# Power.net
KiCad netlist of a schematic drawn in Altium Designer
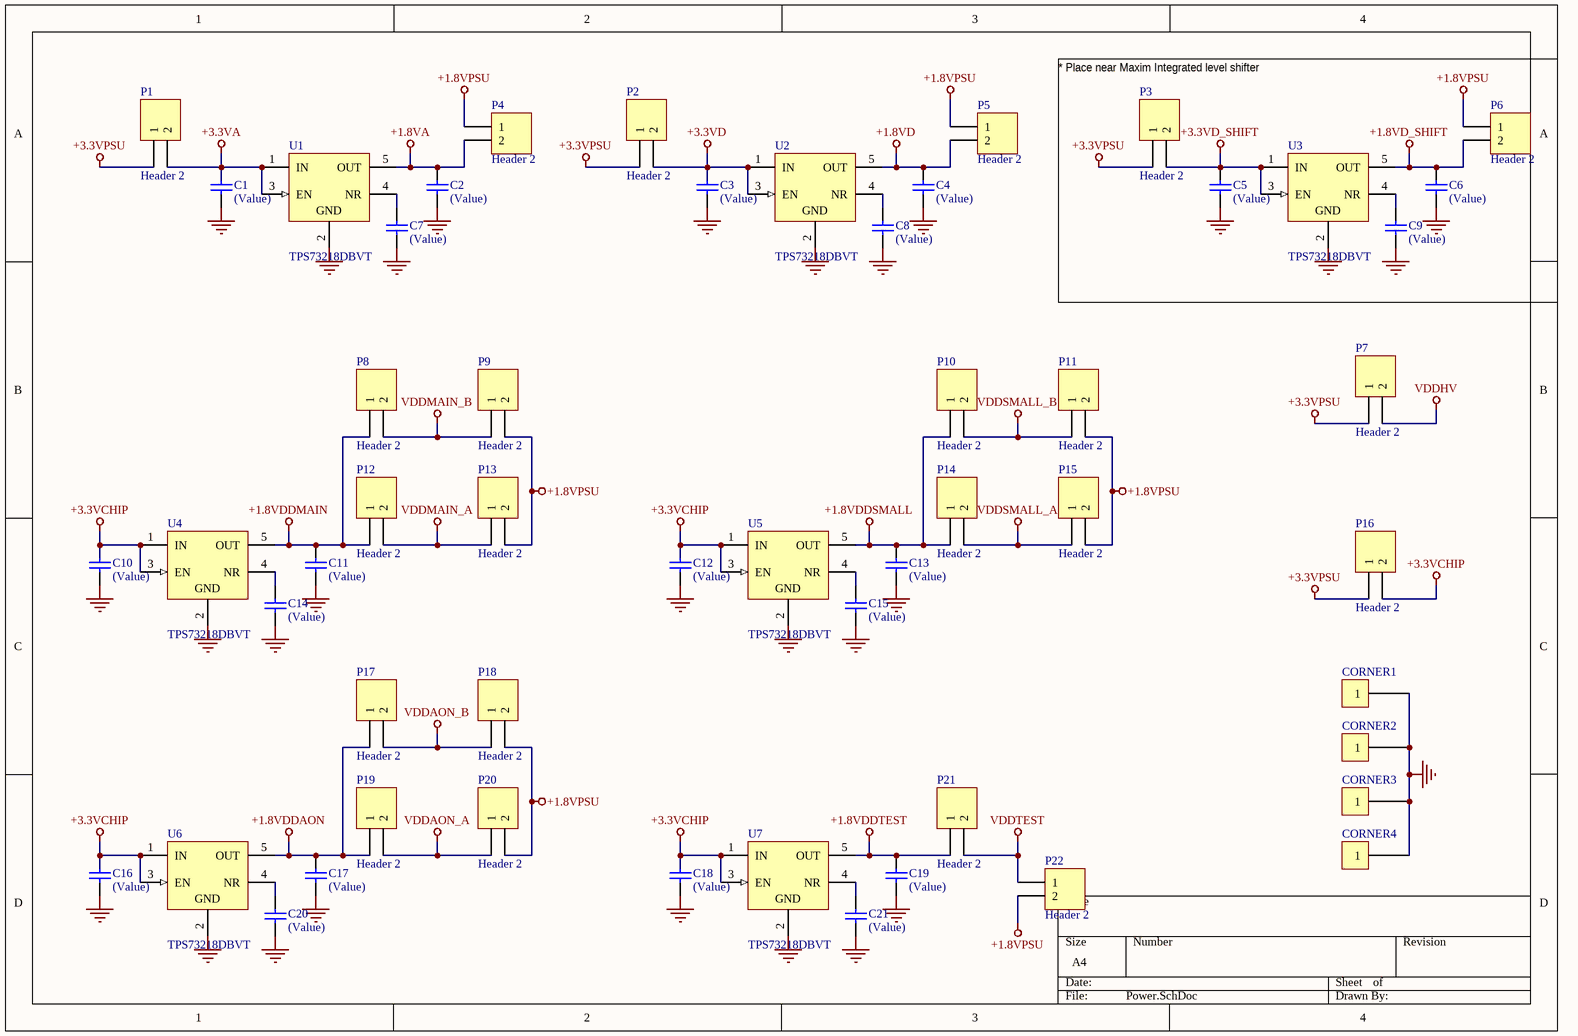
[diagram p0: Power.SchDoc]

(export (version "E")
  (design (tool "Eeschema 10.0.6"))
  (components
    (comp (ref "C1")
      (value "(Value)")
      (footprint "CAPC1608X90X35ML10T15")
      (description "0603")
      (fields (field (name "MANUFACTURER") "Murata"))
      (libsource (lib "Altium Content Vault") (part "CAP-NP-2"))
    )
    (comp (ref "C2")
      (value "(Value)")
      (footprint "CAPC1608X90X35ML10T15")
      (description "0603")
      (fields (field (name "MANUFACTURER") "Murata"))
      (libsource (lib "Altium Content Vault") (part "CAP-NP-2"))
    )
    (comp (ref "C3")
      (value "(Value)")
      (footprint "CAPC1608X90X35ML10T15")
      (description "0603")
      (fields (field (name "MANUFACTURER") "Murata"))
      (libsource (lib "Altium Content Vault") (part "CAP-NP-2"))
    )
    (comp (ref "C4")
      (value "(Value)")
      (footprint "CAPC1608X90X35ML10T15")
      (description "0603")
      (fields (field (name "MANUFACTURER") "Murata"))
      (libsource (lib "Altium Content Vault") (part "CAP-NP-2"))
    )
    (comp (ref "C5")
      (value "(Value)")
      (footprint "CAPC1608X90X35ML10T15")
      (description "0603")
      (fields (field (name "MANUFACTURER") "Murata"))
      (libsource (lib "Altium Content Vault") (part "CAP-NP-2"))
    )
    (comp (ref "C6")
      (value "(Value)")
      (footprint "CAPC1608X90X35ML10T15")
      (description "0603")
      (fields (field (name "MANUFACTURER") "Murata"))
      (libsource (lib "Altium Content Vault") (part "CAP-NP-2"))
    )
    (comp (ref "C7")
      (value "(Value)")
      (footprint "CAPC1608X90X35ML10T15")
      (description "0603")
      (fields (field (name "MANUFACTURER") "Murata"))
      (libsource (lib "Altium Content Vault") (part "CAP-NP-2"))
    )
    (comp (ref "C8")
      (value "(Value)")
      (footprint "CAPC1608X90X35ML10T15")
      (description "0603")
      (fields (field (name "MANUFACTURER") "Murata"))
      (libsource (lib "Altium Content Vault") (part "CAP-NP-2"))
    )
    (comp (ref "C9")
      (value "(Value)")
      (footprint "CAPC1608X90X35ML10T15")
      (description "0603")
      (fields (field (name "MANUFACTURER") "Murata"))
      (libsource (lib "Altium Content Vault") (part "CAP-NP-2"))
    )
    (comp (ref "C10")
      (value "(Value)")
      (footprint "CAPC1608X90X35ML10T15")
      (description "0603")
      (fields (field (name "MANUFACTURER") "Murata"))
      (libsource (lib "Altium Content Vault") (part "CAP-NP-2"))
    )
    (comp (ref "C11")
      (value "(Value)")
      (footprint "CAPC1608X90X35ML10T15")
      (description "0603")
      (fields (field (name "MANUFACTURER") "Murata"))
      (libsource (lib "Altium Content Vault") (part "CAP-NP-2"))
    )
    (comp (ref "C12")
      (value "(Value)")
      (footprint "CAPC1608X90X35ML10T15")
      (description "0603")
      (fields (field (name "MANUFACTURER") "Murata"))
      (libsource (lib "Altium Content Vault") (part "CAP-NP-2"))
    )
    (comp (ref "C13")
      (value "(Value)")
      (footprint "CAPC1608X90X35ML10T15")
      (description "0603")
      (fields (field (name "MANUFACTURER") "Murata"))
      (libsource (lib "Altium Content Vault") (part "CAP-NP-2"))
    )
    (comp (ref "C14")
      (value "(Value)")
      (footprint "CAPC1608X90X35ML10T15")
      (description "0603")
      (fields (field (name "MANUFACTURER") "Murata"))
      (libsource (lib "Altium Content Vault") (part "CAP-NP-2"))
    )
    (comp (ref "C15")
      (value "(Value)")
      (footprint "CAPC1608X90X35ML10T15")
      (description "0603")
      (fields (field (name "MANUFACTURER") "Murata"))
      (libsource (lib "Altium Content Vault") (part "CAP-NP-2"))
    )
    (comp (ref "C16")
      (value "(Value)")
      (footprint "CAPC1608X90X35ML10T15")
      (description "0603")
      (fields (field (name "MANUFACTURER") "Murata"))
      (libsource (lib "Altium Content Vault") (part "CAP-NP-2"))
    )
    (comp (ref "C17")
      (value "(Value)")
      (footprint "CAPC1608X90X35ML10T15")
      (description "0603")
      (fields (field (name "MANUFACTURER") "Murata"))
      (libsource (lib "Altium Content Vault") (part "CAP-NP-2"))
    )
    (comp (ref "C18")
      (value "(Value)")
      (footprint "CAPC1608X90X35ML10T15")
      (description "0603")
      (fields (field (name "MANUFACTURER") "Murata"))
      (libsource (lib "Altium Content Vault") (part "CAP-NP-2"))
    )
    (comp (ref "C19")
      (value "(Value)")
      (footprint "CAPC1608X90X35ML10T15")
      (description "0603")
      (fields (field (name "MANUFACTURER") "Murata"))
      (libsource (lib "Altium Content Vault") (part "CAP-NP-2"))
    )
    (comp (ref "C20")
      (value "(Value)")
      (footprint "CAPC1608X90X35ML10T15")
      (description "0603")
      (fields (field (name "MANUFACTURER") "Murata"))
      (libsource (lib "Altium Content Vault") (part "CAP-NP-2"))
    )
    (comp (ref "C21")
      (value "(Value)")
      (footprint "CAPC1608X90X35ML10T15")
      (description "0603")
      (fields (field (name "MANUFACTURER") "Murata"))
      (libsource (lib "Altium Content Vault") (part "CAP-NP-2"))
    )
    (comp (ref "CORNER1")
      (value "Corner Mount")
      (footprint "CornerMount")
      (libsource (lib "intlib") (part "Corner Mount"))
    )
    (comp (ref "CORNER2")
      (value "Corner Mount")
      (footprint "CornerMount")
      (libsource (lib "intlib") (part "Corner Mount"))
    )
    (comp (ref "CORNER3")
      (value "Corner Mount")
      (footprint "CornerMount")
      (libsource (lib "intlib") (part "Corner Mount"))
    )
    (comp (ref "CORNER4")
      (value "Corner Mount")
      (footprint "CornerMount")
      (libsource (lib "intlib") (part "Corner Mount"))
    )
    (comp (ref "P1")
      (value "Header 2")
      (footprint "HDR1X2")
      (description "Header, 2-Pin")
      (fields (field (name "PUBLISHER") "Altium Limited"))
      (libsource (lib "Miscellaneous Connectors") (part "Header 2"))
    )
    (comp (ref "P2")
      (value "Header 2")
      (footprint "HDR1X2")
      (description "Header, 2-Pin")
      (fields (field (name "PUBLISHER") "Altium Limited"))
      (libsource (lib "Miscellaneous Connectors") (part "Header 2"))
    )
    (comp (ref "P3")
      (value "Header 2")
      (footprint "HDR1X2")
      (description "Header, 2-Pin")
      (fields (field (name "PUBLISHER") "Altium Limited"))
      (libsource (lib "Miscellaneous Connectors") (part "Header 2"))
    )
    (comp (ref "P4")
      (value "Header 2")
      (footprint "HDR1X2")
      (description "Header, 2-Pin")
      (fields (field (name "PUBLISHER") "Altium Limited"))
      (libsource (lib "") (part "Header 2_1"))
    )
    (comp (ref "P5")
      (value "Header 2")
      (footprint "HDR1X2")
      (description "Header, 2-Pin")
      (fields (field (name "PUBLISHER") "Altium Limited"))
      (libsource (lib "") (part "Header 2_1"))
    )
    (comp (ref "P6")
      (value "Header 2")
      (footprint "HDR1X2")
      (description "Header, 2-Pin")
      (fields (field (name "PUBLISHER") "Altium Limited"))
      (libsource (lib "") (part "Header 2_1"))
    )
    (comp (ref "P7")
      (value "Header 2")
      (footprint "HDR1X2")
      (description "Header, 2-Pin")
      (fields (field (name "PUBLISHER") "Altium Limited"))
      (libsource (lib "Miscellaneous Connectors") (part "Header 2"))
    )
    (comp (ref "P8")
      (value "Header 2")
      (footprint "HDR1X2")
      (description "Header, 2-Pin")
      (fields (field (name "PUBLISHER") "Altium Limited"))
      (libsource (lib "Miscellaneous Connectors") (part "Header 2"))
    )
    (comp (ref "P9")
      (value "Header 2")
      (footprint "HDR1X2")
      (description "Header, 2-Pin")
      (fields (field (name "PUBLISHER") "Altium Limited"))
      (libsource (lib "Miscellaneous Connectors") (part "Header 2"))
    )
    (comp (ref "P10")
      (value "Header 2")
      (footprint "HDR1X2")
      (description "Header, 2-Pin")
      (fields (field (name "PUBLISHER") "Altium Limited"))
      (libsource (lib "Miscellaneous Connectors") (part "Header 2"))
    )
    (comp (ref "P11")
      (value "Header 2")
      (footprint "HDR1X2")
      (description "Header, 2-Pin")
      (fields (field (name "PUBLISHER") "Altium Limited"))
      (libsource (lib "Miscellaneous Connectors") (part "Header 2"))
    )
    (comp (ref "P12")
      (value "Header 2")
      (footprint "HDR1X2")
      (description "Header, 2-Pin")
      (fields (field (name "PUBLISHER") "Altium Limited"))
      (libsource (lib "Miscellaneous Connectors") (part "Header 2"))
    )
    (comp (ref "P13")
      (value "Header 2")
      (footprint "HDR1X2")
      (description "Header, 2-Pin")
      (fields (field (name "PUBLISHER") "Altium Limited"))
      (libsource (lib "Miscellaneous Connectors") (part "Header 2"))
    )
    (comp (ref "P14")
      (value "Header 2")
      (footprint "HDR1X2")
      (description "Header, 2-Pin")
      (fields (field (name "PUBLISHER") "Altium Limited"))
      (libsource (lib "Miscellaneous Connectors") (part "Header 2"))
    )
    (comp (ref "P15")
      (value "Header 2")
      (footprint "HDR1X2")
      (description "Header, 2-Pin")
      (fields (field (name "PUBLISHER") "Altium Limited"))
      (libsource (lib "Miscellaneous Connectors") (part "Header 2"))
    )
    (comp (ref "P16")
      (value "Header 2")
      (footprint "HDR1X2")
      (description "Header, 2-Pin")
      (fields (field (name "PUBLISHER") "Altium Limited"))
      (libsource (lib "Miscellaneous Connectors") (part "Header 2"))
    )
    (comp (ref "P17")
      (value "Header 2")
      (footprint "HDR1X2")
      (description "Header, 2-Pin")
      (fields (field (name "PUBLISHER") "Altium Limited"))
      (libsource (lib "Miscellaneous Connectors") (part "Header 2"))
    )
    (comp (ref "P18")
      (value "Header 2")
      (footprint "HDR1X2")
      (description "Header, 2-Pin")
      (fields (field (name "PUBLISHER") "Altium Limited"))
      (libsource (lib "Miscellaneous Connectors") (part "Header 2"))
    )
    (comp (ref "P19")
      (value "Header 2")
      (footprint "HDR1X2")
      (description "Header, 2-Pin")
      (fields (field (name "PUBLISHER") "Altium Limited"))
      (libsource (lib "Miscellaneous Connectors") (part "Header 2"))
    )
    (comp (ref "P20")
      (value "Header 2")
      (footprint "HDR1X2")
      (description "Header, 2-Pin")
      (fields (field (name "PUBLISHER") "Altium Limited"))
      (libsource (lib "Miscellaneous Connectors") (part "Header 2"))
    )
    (comp (ref "P21")
      (value "Header 2")
      (footprint "HDR1X2")
      (description "Header, 2-Pin")
      (fields (field (name "PUBLISHER") "Altium Limited"))
      (libsource (lib "Miscellaneous Connectors") (part "Header 2"))
    )
    (comp (ref "P22")
      (value "Header 2")
      (footprint "HDR1X2")
      (description "Header, 2-Pin")
      (fields (field (name "PUBLISHER") "Altium Limited"))
      (libsource (lib "") (part "Header 2_1"))
    )
    (comp (ref "U1")
      (value "TPS73218DBVT")
      (footprint "DBV0005A_N")
      (fields (field (name "MANUFACTURER") "Texas Instruments"))
      (libsource (lib "Altium Content Vault") (part "TI-TPS79NXX-YYSOT5"))
    )
    (comp (ref "U2")
      (value "TPS73218DBVT")
      (footprint "DBV0005A_N")
      (fields (field (name "MANUFACTURER") "Texas Instruments"))
      (libsource (lib "Altium Content Vault") (part "TI-TPS79NXX-YYSOT5"))
    )
    (comp (ref "U3")
      (value "TPS73218DBVT")
      (footprint "DBV0005A_N")
      (fields (field (name "MANUFACTURER") "Texas Instruments"))
      (libsource (lib "Altium Content Vault") (part "TI-TPS79NXX-YYSOT5"))
    )
    (comp (ref "U4")
      (value "TPS73218DBVT")
      (footprint "DBV0005A_N")
      (fields (field (name "MANUFACTURER") "Texas Instruments"))
      (libsource (lib "Altium Content Vault") (part "TI-TPS79NXX-YYSOT5"))
    )
    (comp (ref "U5")
      (value "TPS73218DBVT")
      (footprint "DBV0005A_N")
      (fields (field (name "MANUFACTURER") "Texas Instruments"))
      (libsource (lib "Altium Content Vault") (part "TI-TPS79NXX-YYSOT5"))
    )
    (comp (ref "U6")
      (value "TPS73218DBVT")
      (footprint "DBV0005A_N")
      (fields (field (name "MANUFACTURER") "Texas Instruments"))
      (libsource (lib "Altium Content Vault") (part "TI-TPS79NXX-YYSOT5"))
    )
    (comp (ref "U7")
      (value "TPS73218DBVT")
      (footprint "DBV0005A_N")
      (fields (field (name "MANUFACTURER") "Texas Instruments"))
      (libsource (lib "Altium Content Vault") (part "TI-TPS79NXX-YYSOT5"))
    )
  )
  (nets
    (net (code "1") (name "+1.8VA") (class "Default")
      (node (ref "C2") (pin "1") (pinfunction "1_1") (pintype "passive"))
      (node (ref "P4") (pin "2") (pinfunction "2_2") (pintype "passive"))
      (node (ref "U1") (pin "5") (pinfunction "OUT_5") (pintype "power_in"))
    )
    (net (code "2") (name "+1.8VD") (class "Default")
      (node (ref "C4") (pin "1") (pinfunction "1_1") (pintype "passive"))
      (node (ref "P5") (pin "2") (pinfunction "2_2") (pintype "passive"))
      (node (ref "U2") (pin "5") (pinfunction "OUT_5") (pintype "power_in"))
    )
    (net (code "3") (name "+1.8VDDAON") (class "Default")
      (node (ref "C17") (pin "1") (pinfunction "1_1") (pintype "passive"))
      (node (ref "P17") (pin "1") (pinfunction "1_1") (pintype "passive"))
      (node (ref "P19") (pin "1") (pinfunction "1_1") (pintype "passive"))
      (node (ref "U6") (pin "5") (pinfunction "OUT_5") (pintype "power_in"))
    )
    (net (code "4") (name "+1.8VDDMAIN") (class "Default")
      (node (ref "C11") (pin "1") (pinfunction "1_1") (pintype "passive"))
      (node (ref "P12") (pin "1") (pinfunction "1_1") (pintype "passive"))
      (node (ref "P8") (pin "1") (pinfunction "1_1") (pintype "passive"))
      (node (ref "U4") (pin "5") (pinfunction "OUT_5") (pintype "power_in"))
    )
    (net (code "5") (name "+1.8VDDSMALL") (class "Default")
      (node (ref "C13") (pin "1") (pinfunction "1_1") (pintype "passive"))
      (node (ref "P10") (pin "1") (pinfunction "1_1") (pintype "passive"))
      (node (ref "P14") (pin "1") (pinfunction "1_1") (pintype "passive"))
      (node (ref "U5") (pin "5") (pinfunction "OUT_5") (pintype "power_in"))
    )
    (net (code "6") (name "+1.8VDDTEST") (class "Default")
      (node (ref "C19") (pin "1") (pinfunction "1_1") (pintype "passive"))
      (node (ref "P21") (pin "1") (pinfunction "1_1") (pintype "passive"))
      (node (ref "U7") (pin "5") (pinfunction "OUT_5") (pintype "power_in"))
    )
    (net (code "7") (name "+1.8VD_SHIFT") (class "Default")
      (node (ref "C6") (pin "1") (pinfunction "1_1") (pintype "passive"))
      (node (ref "P6") (pin "2") (pinfunction "2_2") (pintype "passive"))
      (node (ref "U3") (pin "5") (pinfunction "OUT_5") (pintype "power_in"))
    )
    (net (code "8") (name "+1.8VPSU") (class "Default")
      (node (ref "P11") (pin "2") (pinfunction "2_2") (pintype "passive"))
      (node (ref "P13") (pin "2") (pinfunction "2_2") (pintype "passive"))
      (node (ref "P15") (pin "2") (pinfunction "2_2") (pintype "passive"))
      (node (ref "P18") (pin "2") (pinfunction "2_2") (pintype "passive"))
      (node (ref "P20") (pin "2") (pinfunction "2_2") (pintype "passive"))
      (node (ref "P22") (pin "2") (pinfunction "2_2") (pintype "passive"))
      (node (ref "P4") (pin "1") (pinfunction "1_1") (pintype "passive"))
      (node (ref "P5") (pin "1") (pinfunction "1_1") (pintype "passive"))
      (node (ref "P6") (pin "1") (pinfunction "1_1") (pintype "passive"))
      (node (ref "P9") (pin "2") (pinfunction "2_2") (pintype "passive"))
    )
    (net (code "9") (name "+3.3VA") (class "Default")
      (node (ref "C1") (pin "1") (pinfunction "1_1") (pintype "passive"))
      (node (ref "P1") (pin "2") (pinfunction "2_2") (pintype "passive"))
      (node (ref "U1") (pin "1") (pinfunction "IN_1") (pintype "power_in"))
      (node (ref "U1") (pin "3") (pinfunction "EN_3") (pintype "input"))
    )
    (net (code "10") (name "+3.3VCHIP") (class "Default")
      (node (ref "C10") (pin "1") (pinfunction "1_1") (pintype "passive"))
      (node (ref "C12") (pin "1") (pinfunction "1_1") (pintype "passive"))
      (node (ref "C16") (pin "1") (pinfunction "1_1") (pintype "passive"))
      (node (ref "C18") (pin "1") (pinfunction "1_1") (pintype "passive"))
      (node (ref "P16") (pin "2") (pinfunction "2_2") (pintype "passive"))
      (node (ref "U4") (pin "1") (pinfunction "IN_1") (pintype "power_in"))
      (node (ref "U4") (pin "3") (pinfunction "EN_3") (pintype "input"))
      (node (ref "U5") (pin "1") (pinfunction "IN_1") (pintype "power_in"))
      (node (ref "U5") (pin "3") (pinfunction "EN_3") (pintype "input"))
      (node (ref "U6") (pin "1") (pinfunction "IN_1") (pintype "power_in"))
      (node (ref "U6") (pin "3") (pinfunction "EN_3") (pintype "input"))
      (node (ref "U7") (pin "1") (pinfunction "IN_1") (pintype "power_in"))
      (node (ref "U7") (pin "3") (pinfunction "EN_3") (pintype "input"))
    )
    (net (code "11") (name "+3.3VD") (class "Default")
      (node (ref "C3") (pin "1") (pinfunction "1_1") (pintype "passive"))
      (node (ref "P2") (pin "2") (pinfunction "2_2") (pintype "passive"))
      (node (ref "U2") (pin "1") (pinfunction "IN_1") (pintype "power_in"))
      (node (ref "U2") (pin "3") (pinfunction "EN_3") (pintype "input"))
    )
    (net (code "12") (name "+3.3VD_SHIFT") (class "Default")
      (node (ref "C5") (pin "1") (pinfunction "1_1") (pintype "passive"))
      (node (ref "P3") (pin "2") (pinfunction "2_2") (pintype "passive"))
      (node (ref "U3") (pin "1") (pinfunction "IN_1") (pintype "power_in"))
      (node (ref "U3") (pin "3") (pinfunction "EN_3") (pintype "input"))
    )
    (net (code "13") (name "+3.3VPSU") (class "Default")
      (node (ref "P1") (pin "1") (pinfunction "1_1") (pintype "passive"))
      (node (ref "P16") (pin "1") (pinfunction "1_1") (pintype "passive"))
      (node (ref "P2") (pin "1") (pinfunction "1_1") (pintype "passive"))
      (node (ref "P3") (pin "1") (pinfunction "1_1") (pintype "passive"))
      (node (ref "P7") (pin "1") (pinfunction "1_1") (pintype "passive"))
    )
    (net (code "14") (name "GND") (class "Default")
      (node (ref "C1") (pin "2") (pinfunction "2_2") (pintype "passive"))
      (node (ref "C10") (pin "2") (pinfunction "2_2") (pintype "passive"))
      (node (ref "C11") (pin "2") (pinfunction "2_2") (pintype "passive"))
      (node (ref "C12") (pin "2") (pinfunction "2_2") (pintype "passive"))
      (node (ref "C13") (pin "2") (pinfunction "2_2") (pintype "passive"))
      (node (ref "C14") (pin "2") (pinfunction "2_2") (pintype "passive"))
      (node (ref "C15") (pin "2") (pinfunction "2_2") (pintype "passive"))
      (node (ref "C16") (pin "2") (pinfunction "2_2") (pintype "passive"))
      (node (ref "C17") (pin "2") (pinfunction "2_2") (pintype "passive"))
      (node (ref "C18") (pin "2") (pinfunction "2_2") (pintype "passive"))
      (node (ref "C19") (pin "2") (pinfunction "2_2") (pintype "passive"))
      (node (ref "C2") (pin "2") (pinfunction "2_2") (pintype "passive"))
      (node (ref "C20") (pin "2") (pinfunction "2_2") (pintype "passive"))
      (node (ref "C21") (pin "2") (pinfunction "2_2") (pintype "passive"))
      (node (ref "C3") (pin "2") (pinfunction "2_2") (pintype "passive"))
      (node (ref "C4") (pin "2") (pinfunction "2_2") (pintype "passive"))
      (node (ref "C5") (pin "2") (pinfunction "2_2") (pintype "passive"))
      (node (ref "C6") (pin "2") (pinfunction "2_2") (pintype "passive"))
      (node (ref "C7") (pin "2") (pinfunction "2_2") (pintype "passive"))
      (node (ref "C8") (pin "2") (pinfunction "2_2") (pintype "passive"))
      (node (ref "C9") (pin "2") (pinfunction "2_2") (pintype "passive"))
      (node (ref "CORNER1") (pin "1") (pinfunction "1_1") (pintype "passive"))
      (node (ref "CORNER2") (pin "1") (pinfunction "1_1") (pintype "passive"))
      (node (ref "CORNER3") (pin "1") (pinfunction "1_1") (pintype "passive"))
      (node (ref "CORNER4") (pin "1") (pinfunction "1_1") (pintype "passive"))
      (node (ref "U1") (pin "2") (pinfunction "GND_2") (pintype "power_in"))
      (node (ref "U2") (pin "2") (pinfunction "GND_2") (pintype "power_in"))
      (node (ref "U3") (pin "2") (pinfunction "GND_2") (pintype "power_in"))
      (node (ref "U4") (pin "2") (pinfunction "GND_2") (pintype "power_in"))
      (node (ref "U5") (pin "2") (pinfunction "GND_2") (pintype "power_in"))
      (node (ref "U6") (pin "2") (pinfunction "GND_2") (pintype "power_in"))
      (node (ref "U7") (pin "2") (pinfunction "GND_2") (pintype "power_in"))
    )
    (net (code "15") (name "Net-(U1-NR)") (class "Default")
      (node (ref "C7") (pin "1") (pinfunction "1_1") (pintype "passive"))
      (node (ref "U1") (pin "4") (pinfunction "NR_4") (pintype "passive"))
    )
    (net (code "16") (name "Net-(U2-NR)") (class "Default")
      (node (ref "C8") (pin "1") (pinfunction "1_1") (pintype "passive"))
      (node (ref "U2") (pin "4") (pinfunction "NR_4") (pintype "passive"))
    )
    (net (code "17") (name "Net-(U3-NR)") (class "Default")
      (node (ref "C9") (pin "1") (pinfunction "1_1") (pintype "passive"))
      (node (ref "U3") (pin "4") (pinfunction "NR_4") (pintype "passive"))
    )
    (net (code "18") (name "Net-(U4-NR)") (class "Default")
      (node (ref "C14") (pin "1") (pinfunction "1_1") (pintype "passive"))
      (node (ref "U4") (pin "4") (pinfunction "NR_4") (pintype "passive"))
    )
    (net (code "19") (name "Net-(U5-NR)") (class "Default")
      (node (ref "C15") (pin "1") (pinfunction "1_1") (pintype "passive"))
      (node (ref "U5") (pin "4") (pinfunction "NR_4") (pintype "passive"))
    )
    (net (code "20") (name "Net-(U6-NR)") (class "Default")
      (node (ref "C20") (pin "1") (pinfunction "1_1") (pintype "passive"))
      (node (ref "U6") (pin "4") (pinfunction "NR_4") (pintype "passive"))
    )
    (net (code "21") (name "Net-(U7-NR)") (class "Default")
      (node (ref "C21") (pin "1") (pinfunction "1_1") (pintype "passive"))
      (node (ref "U7") (pin "4") (pinfunction "NR_4") (pintype "passive"))
    )
    (net (code "22") (name "VDDAON_A") (class "Default")
      (node (ref "P19") (pin "2") (pinfunction "2_2") (pintype "passive"))
      (node (ref "P20") (pin "1") (pinfunction "1_1") (pintype "passive"))
    )
    (net (code "23") (name "VDDAON_B") (class "Default")
      (node (ref "P17") (pin "2") (pinfunction "2_2") (pintype "passive"))
      (node (ref "P18") (pin "1") (pinfunction "1_1") (pintype "passive"))
    )
    (net (code "24") (name "VDDHV") (class "Default")
      (node (ref "P7") (pin "2") (pinfunction "2_2") (pintype "passive"))
    )
    (net (code "25") (name "VDDMAIN_A") (class "Default")
      (node (ref "P12") (pin "2") (pinfunction "2_2") (pintype "passive"))
      (node (ref "P13") (pin "1") (pinfunction "1_1") (pintype "passive"))
    )
    (net (code "26") (name "VDDMAIN_B") (class "Default")
      (node (ref "P8") (pin "2") (pinfunction "2_2") (pintype "passive"))
      (node (ref "P9") (pin "1") (pinfunction "1_1") (pintype "passive"))
    )
    (net (code "27") (name "VDDSMALL_A") (class "Default")
      (node (ref "P14") (pin "2") (pinfunction "2_2") (pintype "passive"))
      (node (ref "P15") (pin "1") (pinfunction "1_1") (pintype "passive"))
    )
    (net (code "28") (name "VDDSMALL_B") (class "Default")
      (node (ref "P10") (pin "2") (pinfunction "2_2") (pintype "passive"))
      (node (ref "P11") (pin "1") (pinfunction "1_1") (pintype "passive"))
    )
    (net (code "29") (name "VDDTEST") (class "Default")
      (node (ref "P21") (pin "2") (pinfunction "2_2") (pintype "passive"))
      (node (ref "P22") (pin "1") (pinfunction "1_1") (pintype "passive"))
    )
  )
)
